# LDO.net
KiCad netlist of a schematic drawn in EAGLE
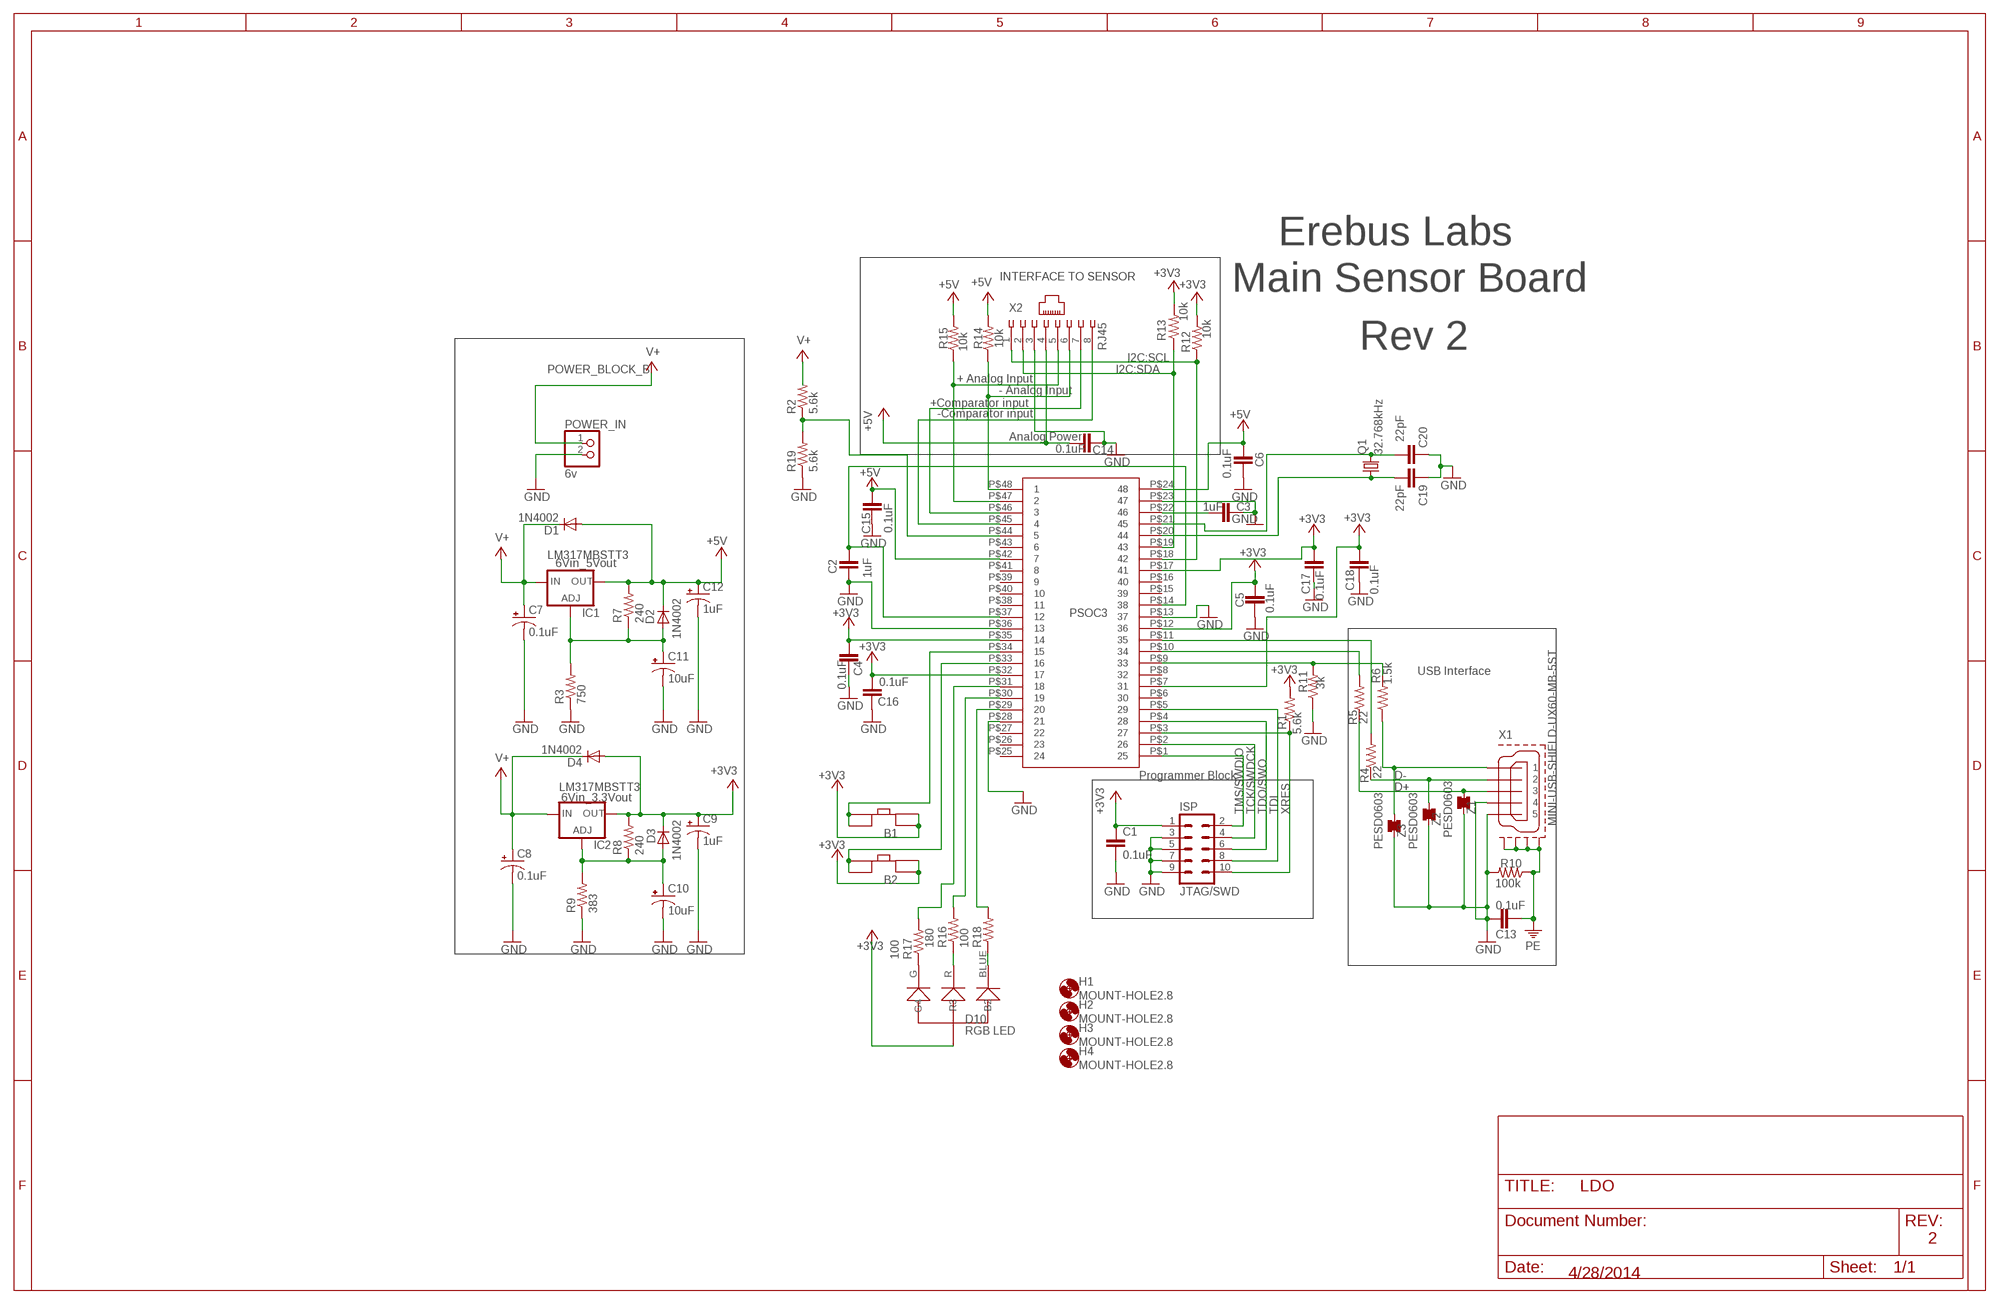
[diagram p0: schematic, sheet 1]

(export (version "E")
  (design (tool "Eeschema 10.0.6"))
  (components
    (comp (ref "C1")
      (value "0.1uF")
      (footprint "eagle-import:C0603K")
      (libsource (lib "eagle-import") (part "C-EUC0603K"))
    )
    (comp (ref "C2")
      (value "1uF")
      (footprint "eagle-import:C0603")
      (libsource (lib "eagle-import") (part "C-EUC0603"))
    )
    (comp (ref "C3")
      (value "1uF")
      (footprint "eagle-import:C0603")
      (libsource (lib "eagle-import") (part "C-EUC0603"))
    )
    (comp (ref "C4")
      (value "0.1uF")
      (footprint "eagle-import:C0603K")
      (libsource (lib "eagle-import") (part "C-EUC0603K"))
    )
    (comp (ref "C5")
      (value "0.1uF")
      (footprint "eagle-import:C0603K")
      (libsource (lib "eagle-import") (part "C-EUC0603K"))
    )
    (comp (ref "C6")
      (value "0.1uF")
      (footprint "eagle-import:C0603K")
      (libsource (lib "eagle-import") (part "C-EUC0603K"))
    )
    (comp (ref "C7")
      (value "0.1uF")
      (footprint "eagle-import:E2-5")
      (libsource (lib "eagle-import") (part "CPOL-USE2-5"))
    )
    (comp (ref "C8")
      (value "0.1uF")
      (footprint "eagle-import:E2-5")
      (libsource (lib "eagle-import") (part "CPOL-USE2-5"))
    )
    (comp (ref "C9")
      (value "1uF")
      (footprint "eagle-import:E2-5")
      (libsource (lib "eagle-import") (part "CPOL-USE2-5"))
    )
    (comp (ref "C10")
      (value "10uF")
      (footprint "eagle-import:E2-5")
      (libsource (lib "eagle-import") (part "CPOL-USE2-5"))
    )
    (comp (ref "C11")
      (value "10uF")
      (footprint "eagle-import:E2-5")
      (libsource (lib "eagle-import") (part "CPOL-USE2-5"))
    )
    (comp (ref "C12")
      (value "1uF")
      (footprint "eagle-import:E2-5")
      (libsource (lib "eagle-import") (part "CPOL-USE2-5"))
    )
    (comp (ref "C13")
      (value "0.1uF")
      (footprint "eagle-import:C0603K")
      (libsource (lib "eagle-import") (part "C-EUC0603K"))
    )
    (comp (ref "C14")
      (value "0.1uF")
      (footprint "eagle-import:C0603K")
      (libsource (lib "eagle-import") (part "C-EUC0603K"))
    )
    (comp (ref "C15")
      (value "0.1uF")
      (footprint "eagle-import:C0603K")
      (libsource (lib "eagle-import") (part "C-EUC0603K"))
    )
    (comp (ref "C16")
      (value "0.1uF")
      (footprint "eagle-import:C0603K")
      (libsource (lib "eagle-import") (part "C-EUC0603K"))
    )
    (comp (ref "C17")
      (value "0.1uF")
      (footprint "eagle-import:C0603K")
      (libsource (lib "eagle-import") (part "C-EUC0603K"))
    )
    (comp (ref "C18")
      (value "0.1uF")
      (footprint "eagle-import:C0603K")
      (libsource (lib "eagle-import") (part "C-EUC0603K"))
    )
    (comp (ref "C19")
      (value "22pF")
      (footprint "eagle-import:C0603")
      (libsource (lib "eagle-import") (part "C-EUC0603"))
    )
    (comp (ref "C20")
      (value "22pF")
      (footprint "eagle-import:C0603")
      (libsource (lib "eagle-import") (part "C-EUC0603"))
    )
    (comp (ref "D1")
      (value "1N4002")
      (footprint "eagle-import:DO41-7.6")
      (libsource (lib "eagle-import") (part "DIODE-DO41-7.6"))
    )
    (comp (ref "D2")
      (value "1N4002")
      (footprint "eagle-import:DO41-7.6")
      (libsource (lib "eagle-import") (part "DIODE-DO41-7.6"))
    )
    (comp (ref "D3")
      (value "1N4002")
      (footprint "eagle-import:DO41-7.6")
      (libsource (lib "eagle-import") (part "DIODE-DO41-7.6"))
    )
    (comp (ref "D4")
      (value "1N4002")
      (footprint "eagle-import:DO41-7.6")
      (libsource (lib "eagle-import") (part "DIODE-DO41-7.6"))
    )
    (comp (ref "D6")
      (value "RGB_LED")
      (footprint "eagle-import:RGB_LED")
      (libsource (lib "eagle-import") (part "RGB_LED"))
    )
    (comp (ref "H1")
      (value "MOUNT-HOLE2.8")
      (footprint "eagle-import:2,8")
      (libsource (lib "eagle-import") (part "MOUNT-HOLE2.8"))
    )
    (comp (ref "H2")
      (value "MOUNT-HOLE2.8")
      (footprint "eagle-import:2,8")
      (libsource (lib "eagle-import") (part "MOUNT-HOLE2.8"))
    )
    (comp (ref "H3")
      (value "MOUNT-HOLE2.8")
      (footprint "eagle-import:2,8")
      (libsource (lib "eagle-import") (part "MOUNT-HOLE2.8"))
    )
    (comp (ref "H4")
      (value "MOUNT-HOLE2.8")
      (footprint "eagle-import:2,8")
      (libsource (lib "eagle-import") (part "MOUNT-HOLE2.8"))
    )
    (comp (ref "IC1")
      (value "LM317MBSTT3")
      (footprint "eagle-import:SOT223")
      (libsource (lib "eagle-import") (part "LM317?MBSTT3"))
    )
    (comp (ref "IC2")
      (value "LM317MBSTT3")
      (footprint "eagle-import:SOT223")
      (libsource (lib "eagle-import") (part "LM317?MBSTT3"))
    )
    (comp (ref "ISP")
      (value "JTAG/SWD")
      (footprint "eagle-import:FTSH-105-01-L-DV-K")
      (libsource (lib "eagle-import") (part "FTSH-105-01-L-DV-K"))
    )
    (comp (ref "POWER_IN")
      (value "6v")
      (footprint "eagle-import:1X02")
      (libsource (lib "eagle-import") (part "PINHD-1X2"))
    )
    (comp (ref "Q1")
      (value "32.768kHz")
      (footprint "eagle-import:TC38H")
      (libsource (lib "eagle-import") (part "CRYSTALTC38H"))
    )
    (comp (ref "R1")
      (value "5.6k")
      (footprint "eagle-import:R0805")
      (libsource (lib "eagle-import") (part "R-US_R0805"))
    )
    (comp (ref "R2")
      (value "5.6k")
      (footprint "eagle-import:R0805")
      (libsource (lib "eagle-import") (part "R-US_R0805"))
    )
    (comp (ref "R3")
      (value "750")
      (footprint "eagle-import:M1206")
      (libsource (lib "eagle-import") (part "R-US_M1206"))
    )
    (comp (ref "R4")
      (value "22")
      (footprint "eagle-import:R0603")
      (libsource (lib "eagle-import") (part "R-US_R0603"))
    )
    (comp (ref "R5")
      (value "22")
      (footprint "eagle-import:R0603")
      (libsource (lib "eagle-import") (part "R-US_R0603"))
    )
    (comp (ref "R6")
      (value "1.5k")
      (footprint "eagle-import:R0805")
      (libsource (lib "eagle-import") (part "R-US_R0805"))
    )
    (comp (ref "R7")
      (value "240")
      (footprint "eagle-import:M1206")
      (libsource (lib "eagle-import") (part "R-US_M1206"))
    )
    (comp (ref "R8")
      (value "240")
      (footprint "eagle-import:M1206")
      (libsource (lib "eagle-import") (part "R-US_M1206"))
    )
    (comp (ref "R9")
      (value "383")
      (footprint "eagle-import:M1206")
      (libsource (lib "eagle-import") (part "R-US_M1206"))
    )
    (comp (ref "R10")
      (value "100k")
      (footprint "eagle-import:R0805")
      (libsource (lib "eagle-import") (part "R-US_R0805"))
    )
    (comp (ref "R11")
      (value "3k")
      (footprint "eagle-import:R0805")
      (libsource (lib "eagle-import") (part "R-US_R0805"))
    )
    (comp (ref "R12")
      (value "10k")
      (footprint "eagle-import:R0805")
      (libsource (lib "eagle-import") (part "R-US_R0805"))
    )
    (comp (ref "R13")
      (value "10k")
      (footprint "eagle-import:R0805")
      (libsource (lib "eagle-import") (part "R-US_R0805"))
    )
    (comp (ref "R14")
      (value "10k")
      (footprint "eagle-import:R0805")
      (libsource (lib "eagle-import") (part "R-US_R0805"))
    )
    (comp (ref "R15")
      (value "10k")
      (footprint "eagle-import:R0805")
      (libsource (lib "eagle-import") (part "R-US_R0805"))
    )
    (comp (ref "R16")
      (value "180")
      (footprint "eagle-import:R0603")
      (libsource (lib "eagle-import") (part "R-US_R0603"))
    )
    (comp (ref "R17")
      (value "100")
      (footprint "eagle-import:R0603")
      (libsource (lib "eagle-import") (part "R-US_R0603"))
    )
    (comp (ref "R18")
      (value "100")
      (footprint "eagle-import:R0603")
      (libsource (lib "eagle-import") (part "R-US_R0603"))
    )
    (comp (ref "R19")
      (value "5.6k")
      (footprint "eagle-import:R0805")
      (libsource (lib "eagle-import") (part "R-US_R0805"))
    )
    (comp (ref "U$1")
      (value "PSOC_3_48PIN_SSOP")
      (footprint "eagle-import:PSOC_3_48PIN_SSOP")
      (libsource (lib "eagle-import") (part "PSOC_3_48PIN_SSOP"))
    )
    (comp (ref "U$5")
      (value "SPST")
      (footprint "eagle-import:SPST")
      (libsource (lib "eagle-import") (part "SPST"))
    )
    (comp (ref "U$6")
      (value "SPST")
      (footprint "eagle-import:SPST")
      (libsource (lib "eagle-import") (part "SPST"))
    )
    (comp (ref "X1")
      (value "MINI-USB-SHIELD-UX60-MB-5ST")
      (footprint "eagle-import:UX60-MB-5ST")
      (libsource (lib "eagle-import") (part "MINI-USB-SHIELD-UX60-MB-5ST"))
    )
    (comp (ref "X2")
      (value "RJ45")
      (footprint "eagle-import:555167-1")
      (libsource (lib "eagle-import") (part "555167-1"))
    )
    (comp (ref "Z1")
      (value "PESD0603")
      (footprint "eagle-import:SMD-0603")
      (libsource (lib "eagle-import") (part "PESD0603"))
    )
    (comp (ref "Z2")
      (value "PESD0603")
      (footprint "eagle-import:SMD-0603")
      (libsource (lib "eagle-import") (part "PESD0603"))
    )
    (comp (ref "Z3")
      (value "PESD0603")
      (footprint "eagle-import:SMD-0603")
      (libsource (lib "eagle-import") (part "PESD0603"))
    )
  )
  (nets
    (net (code "1") (name "+3V3") (class "Default")
      (node (ref "C1") (pin "1") (pinfunction "1_1") (pintype "passive"))
      (node (ref "C16") (pin "2") (pinfunction "2_2") (pintype "passive"))
      (node (ref "C17") (pin "2") (pinfunction "2_2") (pintype "passive"))
      (node (ref "C18") (pin "2") (pinfunction "2_2") (pintype "passive"))
      (node (ref "C4") (pin "2") (pinfunction "2_2") (pintype "passive"))
      (node (ref "C5") (pin "2") (pinfunction "2_2") (pintype "passive"))
      (node (ref "C9") (pin "+") (pinfunction "+_+") (pintype "passive"))
      (node (ref "D3") (pin "C") (pinfunction "C_C") (pintype "passive"))
      (node (ref "D4") (pin "A") (pinfunction "A_A") (pintype "passive"))
      (node (ref "D6") (pin "VCC") (pinfunction "VCC1_VCC") (pintype "bidirectional"))
      (node (ref "IC2") (pin "4") (pinfunction "OUT_4") (pintype "passive"))
      (node (ref "ISP") (pin "1") (pinfunction "1_1") (pintype "passive"))
      (node (ref "R1") (pin "2") (pinfunction "2_2") (pintype "passive"))
      (node (ref "R12") (pin "2") (pinfunction "2_2") (pintype "passive"))
      (node (ref "R13") (pin "2") (pinfunction "2_2") (pintype "passive"))
      (node (ref "R8") (pin "2") (pinfunction "2_2") (pintype "passive"))
      (node (ref "U$1") (pin "P$12") (pinfunction "36_P$12") (pintype "bidirectional"))
      (node (ref "U$1") (pin "P$17") (pinfunction "41_P$17") (pintype "bidirectional"))
      (node (ref "U$1") (pin "P$32") (pinfunction "17_P$32") (pintype "bidirectional"))
      (node (ref "U$1") (pin "P$35") (pinfunction "14_P$35") (pintype "bidirectional"))
      (node (ref "U$1") (pin "P$7") (pinfunction "31_P$7") (pintype "bidirectional"))
      (node (ref "U$5") (pin "B1") (pinfunction "B1_B1") (pintype "bidirectional"))
      (node (ref "U$5") (pin "B2") (pinfunction "B2_B2") (pintype "bidirectional"))
      (node (ref "U$6") (pin "B1") (pinfunction "B1_B1") (pintype "bidirectional"))
      (node (ref "U$6") (pin "B2") (pinfunction "B2_B2") (pintype "bidirectional"))
    )
    (net (code "2") (name "+5V") (class "Default")
      (node (ref "C12") (pin "+") (pinfunction "+_+") (pintype "passive"))
      (node (ref "C14") (pin "2") (pinfunction "2_2") (pintype "passive"))
      (node (ref "C15") (pin "2") (pinfunction "2_2") (pintype "passive"))
      (node (ref "C6") (pin "2") (pinfunction "2_2") (pintype "passive"))
      (node (ref "D1") (pin "A") (pinfunction "A_A") (pintype "passive"))
      (node (ref "D2") (pin "C") (pinfunction "C_C") (pintype "passive"))
      (node (ref "IC1") (pin "4") (pinfunction "OUT_4") (pintype "passive"))
      (node (ref "R14") (pin "2") (pinfunction "2_2") (pintype "passive"))
      (node (ref "R15") (pin "2") (pinfunction "2_2") (pintype "passive"))
      (node (ref "R7") (pin "2") (pinfunction "2_2") (pintype "passive"))
      (node (ref "U$1") (pin "P$24") (pinfunction "48_P$24") (pintype "bidirectional"))
      (node (ref "U$1") (pin "P$42") (pinfunction "7_P$42") (pintype "bidirectional"))
      (node (ref "X2") (pin "4") (pinfunction "4_4") (pintype "passive"))
    )
    (net (code "3") (name "GND") (class "Default")
      (node (ref "C1") (pin "2") (pinfunction "2_2") (pintype "passive"))
      (node (ref "C10") (pin "-") (pinfunction "-_-") (pintype "passive"))
      (node (ref "C11") (pin "-") (pinfunction "-_-") (pintype "passive"))
      (node (ref "C12") (pin "-") (pinfunction "-_-") (pintype "passive"))
      (node (ref "C13") (pin "2") (pinfunction "2_2") (pintype "passive"))
      (node (ref "C14") (pin "1") (pinfunction "1_1") (pintype "passive"))
      (node (ref "C15") (pin "1") (pinfunction "1_1") (pintype "passive"))
      (node (ref "C16") (pin "1") (pinfunction "1_1") (pintype "passive"))
      (node (ref "C17") (pin "1") (pinfunction "1_1") (pintype "passive"))
      (node (ref "C18") (pin "1") (pinfunction "1_1") (pintype "passive"))
      (node (ref "C19") (pin "1") (pinfunction "1_1") (pintype "passive"))
      (node (ref "C2") (pin "1") (pinfunction "1_1") (pintype "passive"))
      (node (ref "C20") (pin "1") (pinfunction "1_1") (pintype "passive"))
      (node (ref "C3") (pin "1") (pinfunction "1_1") (pintype "passive"))
      (node (ref "C4") (pin "1") (pinfunction "1_1") (pintype "passive"))
      (node (ref "C5") (pin "1") (pinfunction "1_1") (pintype "passive"))
      (node (ref "C6") (pin "1") (pinfunction "1_1") (pintype "passive"))
      (node (ref "C7") (pin "-") (pinfunction "-_-") (pintype "passive"))
      (node (ref "C8") (pin "-") (pinfunction "-_-") (pintype "passive"))
      (node (ref "C9") (pin "-") (pinfunction "-_-") (pintype "passive"))
      (node (ref "ISP") (pin "3") (pinfunction "3_3") (pintype "passive"))
      (node (ref "ISP") (pin "5") (pinfunction "5_5") (pintype "passive"))
      (node (ref "ISP") (pin "7") (pinfunction "7_7") (pintype "passive"))
      (node (ref "ISP") (pin "9") (pinfunction "9_9") (pintype "passive"))
      (node (ref "POWER_IN") (pin "2") (pinfunction "2_2") (pintype "passive"))
      (node (ref "R10") (pin "2") (pinfunction "2_2") (pintype "passive"))
      (node (ref "R11") (pin "1") (pinfunction "1_1") (pintype "passive"))
      (node (ref "R19") (pin "1") (pinfunction "1_1") (pintype "passive"))
      (node (ref "R3") (pin "1") (pinfunction "1_1") (pintype "passive"))
      (node (ref "R9") (pin "1") (pinfunction "1_1") (pintype "passive"))
      (node (ref "U$1") (pin "P$13") (pinfunction "37_P$13") (pintype "bidirectional"))
      (node (ref "U$1") (pin "P$23") (pinfunction "47_P$23") (pintype "bidirectional"))
      (node (ref "U$1") (pin "P$28") (pinfunction "21_P$28") (pintype "bidirectional"))
      (node (ref "U$1") (pin "P$36") (pinfunction "13_P$36") (pintype "bidirectional"))
      (node (ref "X1") (pin "4") (pinfunction "4_4") (pintype "input"))
      (node (ref "X1") (pin "5") (pinfunction "5_5") (pintype "input"))
      (node (ref "X2") (pin "3") (pinfunction "3_3") (pintype "passive"))
      (node (ref "Z1") (pin "1") (pinfunction "1_1") (pintype "passive"))
      (node (ref "Z2") (pin "1") (pinfunction "1_1") (pintype "passive"))
      (node (ref "Z3") (pin "1") (pinfunction "1_1") (pintype "passive"))
    )
    (net (code "4") (name "Net-(D6-B2)") (class "Default")
      (node (ref "D6") (pin "BLUE") (pinfunction "B2_BLUE") (pintype "bidirectional"))
      (node (ref "R18") (pin "1") (pinfunction "1_1") (pintype "passive"))
    )
    (net (code "5") (name "Net-(D6-G4)") (class "Default")
      (node (ref "D6") (pin "G") (pinfunction "G4_G") (pintype "bidirectional"))
      (node (ref "R17") (pin "1") (pinfunction "1_1") (pintype "passive"))
    )
    (net (code "6") (name "Net-(D6-R3)") (class "Default")
      (node (ref "D6") (pin "R") (pinfunction "R3_R") (pintype "bidirectional"))
      (node (ref "R16") (pin "1") (pinfunction "1_1") (pintype "passive"))
    )
    (net (code "7") (name "Net-(IC1-ADJ)") (class "Default")
      (node (ref "C11") (pin "+") (pinfunction "+_+") (pintype "passive"))
      (node (ref "D2") (pin "A") (pinfunction "A_A") (pintype "passive"))
      (node (ref "IC1") (pin "1") (pinfunction "ADJ_1") (pintype "input"))
      (node (ref "R3") (pin "2") (pinfunction "2_2") (pintype "passive"))
      (node (ref "R7") (pin "1") (pinfunction "1_1") (pintype "passive"))
    )
    (net (code "8") (name "Net-(IC2-ADJ)") (class "Default")
      (node (ref "C10") (pin "+") (pinfunction "+_+") (pintype "passive"))
      (node (ref "D3") (pin "A") (pinfunction "A_A") (pintype "passive"))
      (node (ref "IC2") (pin "1") (pinfunction "ADJ_1") (pintype "input"))
      (node (ref "R8") (pin "1") (pinfunction "1_1") (pintype "passive"))
      (node (ref "R9") (pin "2") (pinfunction "2_2") (pintype "passive"))
    )
    (net (code "9") (name "Net-(R4-Pad1)") (class "Default")
      (node (ref "R4") (pin "1") (pinfunction "1_1") (pintype "passive"))
      (node (ref "X1") (pin "2") (pinfunction "2_2") (pintype "input"))
      (node (ref "Z2") (pin "2") (pinfunction "2_2") (pintype "passive"))
    )
    (net (code "10") (name "Net-(R5-Pad1)") (class "Default")
      (node (ref "R5") (pin "1") (pinfunction "1_1") (pintype "passive"))
      (node (ref "X1") (pin "3") (pinfunction "3_3") (pintype "input"))
      (node (ref "Z1") (pin "2") (pinfunction "2_2") (pintype "passive"))
    )
    (net (code "11") (name "Net-(R6-Pad1)") (class "Default")
      (node (ref "R6") (pin "1") (pinfunction "1_1") (pintype "passive"))
      (node (ref "X1") (pin "1") (pinfunction "1_1") (pintype "input"))
      (node (ref "Z3") (pin "2") (pinfunction "2_2") (pintype "passive"))
    )
    (net (code "12") (name "Net-(U$1-1)") (class "Default")
      (node (ref "R14") (pin "1") (pinfunction "1_1") (pintype "passive"))
      (node (ref "U$1") (pin "P$48") (pinfunction "1_P$48") (pintype "bidirectional"))
      (node (ref "X2") (pin "6") (pinfunction "6_6") (pintype "passive"))
    )
    (net (code "13") (name "Net-(U$1-2)") (class "Default")
      (node (ref "R15") (pin "1") (pinfunction "1_1") (pintype "passive"))
      (node (ref "U$1") (pin "P$47") (pinfunction "2_P$47") (pintype "bidirectional"))
      (node (ref "X2") (pin "5") (pinfunction "5_5") (pintype "passive"))
    )
    (net (code "14") (name "Net-(U$1-3)") (class "Default")
      (node (ref "U$1") (pin "P$46") (pinfunction "3_P$46") (pintype "bidirectional"))
      (node (ref "X2") (pin "7") (pinfunction "7_7") (pintype "passive"))
    )
    (net (code "15") (name "Net-(U$1-4)") (class "Default")
      (node (ref "U$1") (pin "P$45") (pinfunction "4_P$45") (pintype "bidirectional"))
      (node (ref "X2") (pin "8") (pinfunction "8_8") (pintype "passive"))
    )
    (net (code "16") (name "Net-(U$1-5)") (class "Default")
      (node (ref "R19") (pin "2") (pinfunction "2_2") (pintype "passive"))
      (node (ref "R2") (pin "1") (pinfunction "1_1") (pintype "passive"))
      (node (ref "U$1") (pin "P$44") (pinfunction "5_P$44") (pintype "bidirectional"))
    )
    (net (code "17") (name "Net-(U$1-12)") (class "Default")
      (node (ref "C2") (pin "2") (pinfunction "2_2") (pintype "passive"))
      (node (ref "U$1") (pin "P$14") (pinfunction "38_P$14") (pintype "bidirectional"))
      (node (ref "U$1") (pin "P$37") (pinfunction "12_P$37") (pintype "bidirectional"))
    )
    (net (code "18") (name "Net-(U$1-15)") (class "Default")
      (node (ref "U$1") (pin "P$34") (pinfunction "15_P$34") (pintype "bidirectional"))
      (node (ref "U$5") (pin "A1") (pinfunction "A1_A1") (pintype "bidirectional"))
      (node (ref "U$5") (pin "A2") (pinfunction "A2_A2") (pintype "bidirectional"))
    )
    (net (code "19") (name "Net-(U$1-16)") (class "Default")
      (node (ref "U$1") (pin "P$33") (pinfunction "16_P$33") (pintype "bidirectional"))
      (node (ref "U$6") (pin "A1") (pinfunction "A1_A1") (pintype "bidirectional"))
      (node (ref "U$6") (pin "A2") (pinfunction "A2_A2") (pintype "bidirectional"))
    )
    (net (code "20") (name "Net-(U$1-18)") (class "Default")
      (node (ref "R17") (pin "2") (pinfunction "2_2") (pintype "passive"))
      (node (ref "U$1") (pin "P$31") (pinfunction "18_P$31") (pintype "bidirectional"))
    )
    (net (code "21") (name "Net-(U$1-19)") (class "Default")
      (node (ref "R16") (pin "2") (pinfunction "2_2") (pintype "passive"))
      (node (ref "U$1") (pin "P$30") (pinfunction "19_P$30") (pintype "bidirectional"))
    )
    (net (code "22") (name "Net-(U$1-20)") (class "Default")
      (node (ref "R18") (pin "2") (pinfunction "2_2") (pintype "passive"))
      (node (ref "U$1") (pin "P$29") (pinfunction "20_P$29") (pintype "bidirectional"))
    )
    (net (code "23") (name "Net-(U$1-25)") (class "Default")
      (node (ref "ISP") (pin "2") (pinfunction "2_2") (pintype "passive"))
      (node (ref "U$1") (pin "P$1") (pinfunction "25_P$1") (pintype "bidirectional"))
    )
    (net (code "24") (name "Net-(U$1-26)") (class "Default")
      (node (ref "ISP") (pin "4") (pinfunction "4_4") (pintype "passive"))
      (node (ref "U$1") (pin "P$2") (pinfunction "26_P$2") (pintype "bidirectional"))
    )
    (net (code "25") (name "Net-(U$1-27)") (class "Default")
      (node (ref "ISP") (pin "10") (pinfunction "10_10") (pintype "passive"))
      (node (ref "R1") (pin "1") (pinfunction "1_1") (pintype "passive"))
      (node (ref "U$1") (pin "P$3") (pinfunction "27_P$3") (pintype "bidirectional"))
    )
    (net (code "26") (name "Net-(U$1-28)") (class "Default")
      (node (ref "ISP") (pin "6") (pinfunction "6_6") (pintype "passive"))
      (node (ref "U$1") (pin "P$4") (pinfunction "28_P$4") (pintype "bidirectional"))
    )
    (net (code "27") (name "Net-(U$1-29)") (class "Default")
      (node (ref "ISP") (pin "8") (pinfunction "8_8") (pintype "passive"))
      (node (ref "U$1") (pin "P$5") (pinfunction "29_P$5") (pintype "bidirectional"))
    )
    (net (code "28") (name "Net-(U$1-33)") (class "Default")
      (node (ref "R11") (pin "2") (pinfunction "2_2") (pintype "passive"))
      (node (ref "R6") (pin "2") (pinfunction "2_2") (pintype "passive"))
      (node (ref "U$1") (pin "P$9") (pinfunction "33_P$9") (pintype "bidirectional"))
    )
    (net (code "29") (name "Net-(U$1-34)") (class "Default")
      (node (ref "R5") (pin "2") (pinfunction "2_2") (pintype "passive"))
      (node (ref "U$1") (pin "P$10") (pinfunction "34_P$10") (pintype "bidirectional"))
    )
    (net (code "30") (name "Net-(U$1-35)") (class "Default")
      (node (ref "R4") (pin "2") (pinfunction "2_2") (pintype "passive"))
      (node (ref "U$1") (pin "P$11") (pinfunction "35_P$11") (pintype "bidirectional"))
    )
    (net (code "31") (name "Net-(U$1-42)") (class "Default")
      (node (ref "R12") (pin "1") (pinfunction "1_1") (pintype "passive"))
      (node (ref "U$1") (pin "P$18") (pinfunction "42_P$18") (pintype "bidirectional"))
      (node (ref "X2") (pin "1") (pinfunction "1_1") (pintype "passive"))
    )
    (net (code "32") (name "Net-(U$1-43)") (class "Default")
      (node (ref "R13") (pin "1") (pinfunction "1_1") (pintype "passive"))
      (node (ref "U$1") (pin "P$19") (pinfunction "43_P$19") (pintype "bidirectional"))
      (node (ref "X2") (pin "2") (pinfunction "2_2") (pintype "passive"))
    )
    (net (code "33") (name "Net-(U$1-44)") (class "Default")
      (node (ref "C19") (pin "2") (pinfunction "2_2") (pintype "passive"))
      (node (ref "Q1") (pin "1") (pinfunction "1_1") (pintype "passive"))
      (node (ref "U$1") (pin "P$20") (pinfunction "44_P$20") (pintype "bidirectional"))
    )
    (net (code "34") (name "Net-(U$1-45)") (class "Default")
      (node (ref "C20") (pin "2") (pinfunction "2_2") (pintype "passive"))
      (node (ref "Q1") (pin "2") (pinfunction "2_2") (pintype "passive"))
      (node (ref "U$1") (pin "P$21") (pinfunction "45_P$21") (pintype "bidirectional"))
    )
    (net (code "35") (name "Net-(U$1-46)") (class "Default")
      (node (ref "C3") (pin "2") (pinfunction "2_2") (pintype "passive"))
      (node (ref "U$1") (pin "P$22") (pinfunction "46_P$22") (pintype "bidirectional"))
    )
    (net (code "36") (name "PE") (class "Default")
      (node (ref "C13") (pin "1") (pinfunction "1_1") (pintype "passive"))
      (node (ref "R10") (pin "1") (pinfunction "1_1") (pintype "passive"))
      (node (ref "X1") (pin "M1") (pinfunction "GND1_M1") (pintype "bidirectional"))
      (node (ref "X1") (pin "M2") (pinfunction "GND2_M2") (pintype "bidirectional"))
      (node (ref "X1") (pin "M3") (pinfunction "GND3_M3") (pintype "bidirectional"))
      (node (ref "X1") (pin "M4") (pinfunction "GND4_M4") (pintype "bidirectional"))
    )
    (net (code "37") (name "V+") (class "Default")
      (node (ref "C7") (pin "+") (pinfunction "+_+") (pintype "passive"))
      (node (ref "C8") (pin "+") (pinfunction "+_+") (pintype "passive"))
      (node (ref "D1") (pin "C") (pinfunction "C_C") (pintype "passive"))
      (node (ref "D4") (pin "C") (pinfunction "C_C") (pintype "passive"))
      (node (ref "IC1") (pin "3") (pinfunction "IN_3") (pintype "input"))
      (node (ref "IC2") (pin "3") (pinfunction "IN_3") (pintype "input"))
      (node (ref "POWER_IN") (pin "1") (pinfunction "1_1") (pintype "passive"))
      (node (ref "R2") (pin "2") (pinfunction "2_2") (pintype "passive"))
    )
    (net (code "38") (name "unconnected-(U$1-6-PadP$43)") (class "Default")
      (node (ref "U$1") (pin "P$43") (pinfunction "6_P$43") (pintype "bidirectional"))
    )
    (net (code "39") (name "unconnected-(U$1-8-PadP$41)") (class "Default")
      (node (ref "U$1") (pin "P$41") (pinfunction "8_P$41") (pintype "bidirectional"))
    )
    (net (code "40") (name "unconnected-(U$1-9-PadP$39)") (class "Default")
      (node (ref "U$1") (pin "P$39") (pinfunction "9_P$39") (pintype "bidirectional"))
    )
    (net (code "41") (name "unconnected-(U$1-10-PadP$40)") (class "Default")
      (node (ref "U$1") (pin "P$40") (pinfunction "10_P$40") (pintype "bidirectional"))
    )
    (net (code "42") (name "unconnected-(U$1-11-PadP$38)") (class "Default")
      (node (ref "U$1") (pin "P$38") (pinfunction "11_P$38") (pintype "bidirectional"))
    )
    (net (code "43") (name "unconnected-(U$1-22-PadP$27)") (class "Default")
      (node (ref "U$1") (pin "P$27") (pinfunction "22_P$27") (pintype "bidirectional"))
    )
    (net (code "44") (name "unconnected-(U$1-23-PadP$26)") (class "Default")
      (node (ref "U$1") (pin "P$26") (pinfunction "23_P$26") (pintype "bidirectional"))
    )
    (net (code "45") (name "unconnected-(U$1-24-PadP$25)") (class "Default")
      (node (ref "U$1") (pin "P$25") (pinfunction "24_P$25") (pintype "bidirectional"))
    )
    (net (code "46") (name "unconnected-(U$1-30-PadP$6)") (class "Default")
      (node (ref "U$1") (pin "P$6") (pinfunction "30_P$6") (pintype "bidirectional"))
    )
    (net (code "47") (name "unconnected-(U$1-32-PadP$8)") (class "Default")
      (node (ref "U$1") (pin "P$8") (pinfunction "32_P$8") (pintype "bidirectional"))
    )
    (net (code "48") (name "unconnected-(U$1-39-PadP$15)") (class "Default")
      (node (ref "U$1") (pin "P$15") (pinfunction "39_P$15") (pintype "bidirectional"))
    )
    (net (code "49") (name "unconnected-(U$1-40-PadP$16)") (class "Default")
      (node (ref "U$1") (pin "P$16") (pinfunction "40_P$16") (pintype "bidirectional"))
    )
  )
)
